# audio-mixer-smd.net
KiCad netlist of a schematic drawn in EAGLE
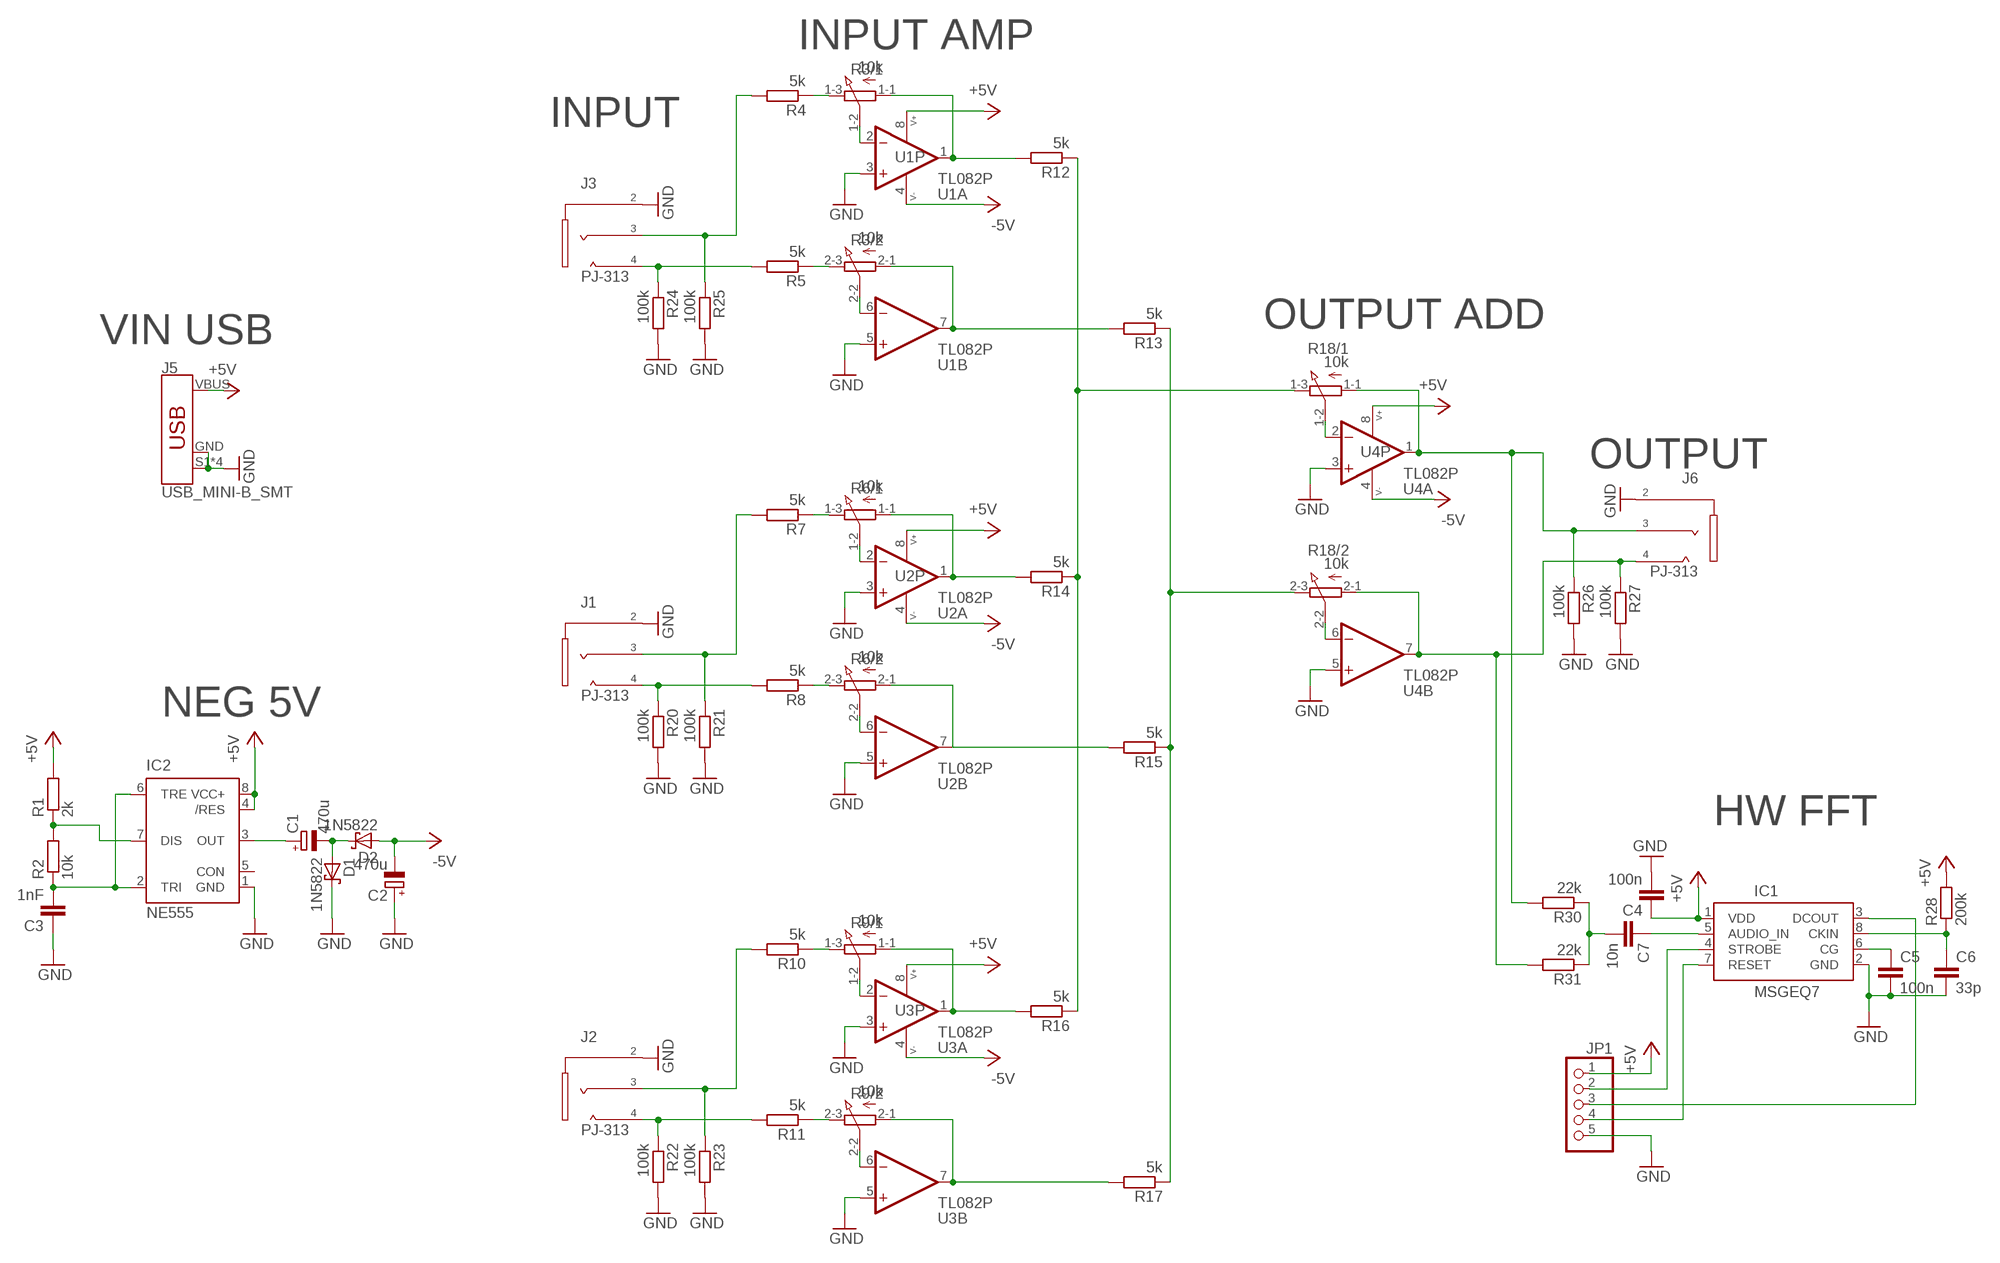
[diagram p0: schematic, sheet 1]

(export (version "E")
  (design (tool "Eeschema 10.0.6"))
  (components
    (comp (ref "C1")
      (value "470u")
      (footprint "eagle-import:E5-8,5")
      (libsource (lib "eagle-import") (part "CPOL-EUE5-8.5"))
    )
    (comp (ref "C2")
      (value "470u")
      (footprint "eagle-import:E5-8,5")
      (libsource (lib "eagle-import") (part "CPOL-EUE5-8.5"))
    )
    (comp (ref "C3")
      (value "1nF")
      (footprint "eagle-import:C0805")
      (libsource (lib "eagle-import") (part "C-EUC0805"))
    )
    (comp (ref "C4")
      (value "100n")
      (footprint "eagle-import:C0805")
      (libsource (lib "eagle-import") (part "C-EUC0805"))
    )
    (comp (ref "C5")
      (value "100n")
      (footprint "eagle-import:C0805")
      (libsource (lib "eagle-import") (part "C-EUC0805"))
    )
    (comp (ref "C6")
      (value "33p")
      (footprint "eagle-import:C0805")
      (libsource (lib "eagle-import") (part "C-EUC0805"))
    )
    (comp (ref "C7")
      (value "10n")
      (footprint "eagle-import:C0805")
      (libsource (lib "eagle-import") (part "C-EUC0805"))
    )
    (comp (ref "D1")
      (value "1N5822")
      (footprint "eagle-import:DO41-7.6")
      (libsource (lib "eagle-import") (part "1N5817-B"))
    )
    (comp (ref "D2")
      (value "1N5822")
      (footprint "eagle-import:DO41-7.6")
      (libsource (lib "eagle-import") (part "1N5817-B"))
    )
    (comp (ref "IC1")
      (value "MSGEQ7DIP")
      (footprint "eagle-import:DIL08")
      (libsource (lib "eagle-import") (part "MSGEQ7DIP"))
    )
    (comp (ref "IC2")
      (value "NE555")
      (footprint "eagle-import:DIL-08")
      (fields (field (name "MF") "Arrow Electronics") (field (name "MPN") "NE555N"))
      (libsource (lib "eagle-import") (part "NE555"))
    )
    (comp (ref "J1")
      (value "PJ-313")
      (footprint "eagle-import:PJ-313")
      (libsource (lib "eagle-import") (part "PJ-313"))
    )
    (comp (ref "J2")
      (value "PJ-313")
      (footprint "eagle-import:PJ-313")
      (libsource (lib "eagle-import") (part "PJ-313"))
    )
    (comp (ref "J3")
      (value "PJ-313")
      (footprint "eagle-import:PJ-313")
      (libsource (lib "eagle-import") (part "PJ-313"))
    )
    (comp (ref "J5")
      (value "USB_MINI-B_SMT")
      (footprint "eagle-import:USB-MINIB")
      (libsource (lib "eagle-import") (part "USB_MINI-B_SMT"))
    )
    (comp (ref "J6")
      (value "PJ-313")
      (footprint "eagle-import:PJ-313")
      (libsource (lib "eagle-import") (part "PJ-313"))
    )
    (comp (ref "JP1")
      (value "PINHD-1X05_2.54-S")
      (footprint "eagle-import:1X05-S")
      (libsource (lib "eagle-import") (part "PINHD-1X05_2.54-S"))
    )
    (comp (ref "R1")
      (value "2k")
      (footprint "eagle-import:R0805")
      (libsource (lib "eagle-import") (part "R-EU_R0805"))
    )
    (comp (ref "R2")
      (value "10k")
      (footprint "eagle-import:R0805")
      (libsource (lib "eagle-import") (part "R-EU_R0805"))
    )
    (comp (ref "R3")
      (value "10k")
      (footprint "eagle-import:3RP_1610G")
      (libsource (lib "eagle-import") (part "3RP/1610G"))
    )
    (comp (ref "R4")
      (value "5k")
      (footprint "eagle-import:R0805")
      (libsource (lib "eagle-import") (part "R-EU_R0805"))
    )
    (comp (ref "R5")
      (value "5k")
      (footprint "eagle-import:R0805")
      (libsource (lib "eagle-import") (part "R-EU_R0805"))
    )
    (comp (ref "R6")
      (value "10k")
      (footprint "eagle-import:3RP_1610G")
      (libsource (lib "eagle-import") (part "3RP/1610G"))
    )
    (comp (ref "R7")
      (value "5k")
      (footprint "eagle-import:R0805")
      (libsource (lib "eagle-import") (part "R-EU_R0805"))
    )
    (comp (ref "R8")
      (value "5k")
      (footprint "eagle-import:R0805")
      (libsource (lib "eagle-import") (part "R-EU_R0805"))
    )
    (comp (ref "R9")
      (value "10k")
      (footprint "eagle-import:3RP_1610G")
      (libsource (lib "eagle-import") (part "3RP/1610G"))
    )
    (comp (ref "R10")
      (value "5k")
      (footprint "eagle-import:R0805")
      (libsource (lib "eagle-import") (part "R-EU_R0805"))
    )
    (comp (ref "R11")
      (value "5k")
      (footprint "eagle-import:R0805")
      (libsource (lib "eagle-import") (part "R-EU_R0805"))
    )
    (comp (ref "R12")
      (value "5k")
      (footprint "eagle-import:R0805")
      (libsource (lib "eagle-import") (part "R-EU_R0805"))
    )
    (comp (ref "R13")
      (value "5k")
      (footprint "eagle-import:R0805")
      (libsource (lib "eagle-import") (part "R-EU_R0805"))
    )
    (comp (ref "R14")
      (value "5k")
      (footprint "eagle-import:R0805")
      (libsource (lib "eagle-import") (part "R-EU_R0805"))
    )
    (comp (ref "R15")
      (value "5k")
      (footprint "eagle-import:R0805")
      (libsource (lib "eagle-import") (part "R-EU_R0805"))
    )
    (comp (ref "R16")
      (value "5k")
      (footprint "eagle-import:R0805")
      (libsource (lib "eagle-import") (part "R-EU_R0805"))
    )
    (comp (ref "R17")
      (value "5k")
      (footprint "eagle-import:R0805")
      (libsource (lib "eagle-import") (part "R-EU_R0805"))
    )
    (comp (ref "R18")
      (value "10k")
      (footprint "eagle-import:3RP_1610G")
      (libsource (lib "eagle-import") (part "3RP/1610G"))
    )
    (comp (ref "R20")
      (value "100k")
      (footprint "eagle-import:R0805")
      (libsource (lib "eagle-import") (part "R-EU_R0805"))
    )
    (comp (ref "R21")
      (value "100k")
      (footprint "eagle-import:R0805")
      (libsource (lib "eagle-import") (part "R-EU_R0805"))
    )
    (comp (ref "R22")
      (value "100k")
      (footprint "eagle-import:R0805")
      (libsource (lib "eagle-import") (part "R-EU_R0805"))
    )
    (comp (ref "R23")
      (value "100k")
      (footprint "eagle-import:R0805")
      (libsource (lib "eagle-import") (part "R-EU_R0805"))
    )
    (comp (ref "R24")
      (value "100k")
      (footprint "eagle-import:R0805")
      (libsource (lib "eagle-import") (part "R-EU_R0805"))
    )
    (comp (ref "R25")
      (value "100k")
      (footprint "eagle-import:R0805")
      (libsource (lib "eagle-import") (part "R-EU_R0805"))
    )
    (comp (ref "R26")
      (value "100k")
      (footprint "eagle-import:R0805")
      (libsource (lib "eagle-import") (part "R-EU_R0805"))
    )
    (comp (ref "R27")
      (value "100k")
      (footprint "eagle-import:R0805")
      (libsource (lib "eagle-import") (part "R-EU_R0805"))
    )
    (comp (ref "R28")
      (value "200k")
      (footprint "eagle-import:R0805")
      (libsource (lib "eagle-import") (part "R-EU_R0805"))
    )
    (comp (ref "R30")
      (value "22k")
      (footprint "eagle-import:R0805")
      (libsource (lib "eagle-import") (part "R-EU_R0805"))
    )
    (comp (ref "R31")
      (value "22k")
      (footprint "eagle-import:R0805")
      (libsource (lib "eagle-import") (part "R-EU_R0805"))
    )
    (comp (ref "U1")
      (value "TL082P")
      (footprint "eagle-import:DIL08")
      (libsource (lib "eagle-import") (part "TL082P"))
    )
    (comp (ref "U2")
      (value "TL082P")
      (footprint "eagle-import:DIL08")
      (libsource (lib "eagle-import") (part "TL082P"))
    )
    (comp (ref "U3")
      (value "TL082P")
      (footprint "eagle-import:DIL08")
      (libsource (lib "eagle-import") (part "TL082P"))
    )
    (comp (ref "U4")
      (value "TL082P")
      (footprint "eagle-import:DIL08")
      (libsource (lib "eagle-import") (part "TL082P"))
    )
  )
  (nets
    (net (code "1") (name "+5V") (class "Default")
      (node (ref "C4") (pin "1") (pinfunction "1_1") (pintype "passive"))
      (node (ref "IC1") (pin "1") (pinfunction "VDD_1") (pintype "input"))
      (node (ref "IC2") (pin "4") (pinfunction "/RES_4") (pintype "input"))
      (node (ref "IC2") (pin "8") (pinfunction "VCC+_8") (pintype "power_in"))
      (node (ref "J5") (pin "VBUS") (pinfunction "VBUS_VBUS") (pintype "power_in"))
      (node (ref "JP1") (pin "1") (pinfunction "1_1") (pintype "passive"))
      (node (ref "R1") (pin "2") (pinfunction "2_2") (pintype "passive"))
      (node (ref "R28") (pin "2") (pinfunction "2_2") (pintype "passive"))
      (node (ref "U1") (pin "8") (pinfunction "V+_8") (pintype "power_in"))
      (node (ref "U2") (pin "8") (pinfunction "V+_8") (pintype "power_in"))
      (node (ref "U3") (pin "8") (pinfunction "V+_8") (pintype "power_in"))
      (node (ref "U4") (pin "8") (pinfunction "V+_8") (pintype "power_in"))
    )
    (net (code "2") (name "-5V") (class "Default")
      (node (ref "C2") (pin "-") (pinfunction "-_-") (pintype "passive"))
      (node (ref "D2") (pin "A") (pinfunction "A_A") (pintype "passive"))
      (node (ref "U1") (pin "4") (pinfunction "V-_4") (pintype "power_in"))
      (node (ref "U2") (pin "4") (pinfunction "V-_4") (pintype "power_in"))
      (node (ref "U3") (pin "4") (pinfunction "V-_4") (pintype "power_in"))
      (node (ref "U4") (pin "4") (pinfunction "V-_4") (pintype "power_in"))
    )
    (net (code "3") (name "GND") (class "Default")
      (node (ref "C2") (pin "+") (pinfunction "+_+") (pintype "passive"))
      (node (ref "C3") (pin "1") (pinfunction "1_1") (pintype "passive"))
      (node (ref "C4") (pin "2") (pinfunction "2_2") (pintype "passive"))
      (node (ref "C5") (pin "2") (pinfunction "2_2") (pintype "passive"))
      (node (ref "C6") (pin "2") (pinfunction "2_2") (pintype "passive"))
      (node (ref "D1") (pin "C") (pinfunction "C_C") (pintype "passive"))
      (node (ref "IC1") (pin "2") (pinfunction "GND_2") (pintype "bidirectional"))
      (node (ref "IC2") (pin "1") (pinfunction "GND_1") (pintype "power_in"))
      (node (ref "J1") (pin "2_1") (pinfunction "2_2_1") (pintype "passive"))
      (node (ref "J1") (pin "2_2") (pinfunction "2_2_2") (pintype "passive"))
      (node (ref "J2") (pin "2_1") (pinfunction "2_2_1") (pintype "passive"))
      (node (ref "J2") (pin "2_2") (pinfunction "2_2_2") (pintype "passive"))
      (node (ref "J3") (pin "2_1") (pinfunction "2_2_1") (pintype "passive"))
      (node (ref "J3") (pin "2_2") (pinfunction "2_2_2") (pintype "passive"))
      (node (ref "J5") (pin "GND") (pinfunction "GND_GND") (pintype "power_in"))
      (node (ref "J5") (pin "S1") (pinfunction "SHIELD_S1") (pintype "bidirectional"))
      (node (ref "J5") (pin "S2") (pinfunction "SHIELD_S2") (pintype "bidirectional"))
      (node (ref "J5") (pin "S3") (pinfunction "SHIELD_S3") (pintype "bidirectional"))
      (node (ref "J5") (pin "S4") (pinfunction "SHIELD_S4") (pintype "bidirectional"))
      (node (ref "J6") (pin "2_1") (pinfunction "2_2_1") (pintype "passive"))
      (node (ref "J6") (pin "2_2") (pinfunction "2_2_2") (pintype "passive"))
      (node (ref "JP1") (pin "5") (pinfunction "5_5") (pintype "passive"))
      (node (ref "R20") (pin "2") (pinfunction "2_2") (pintype "passive"))
      (node (ref "R21") (pin "2") (pinfunction "2_2") (pintype "passive"))
      (node (ref "R22") (pin "2") (pinfunction "2_2") (pintype "passive"))
      (node (ref "R23") (pin "2") (pinfunction "2_2") (pintype "passive"))
      (node (ref "R24") (pin "2") (pinfunction "2_2") (pintype "passive"))
      (node (ref "R25") (pin "2") (pinfunction "2_2") (pintype "passive"))
      (node (ref "R26") (pin "2") (pinfunction "2_2") (pintype "passive"))
      (node (ref "R27") (pin "2") (pinfunction "2_2") (pintype "passive"))
      (node (ref "U1") (pin "3") (pinfunction "+IN_3") (pintype "input"))
      (node (ref "U1") (pin "5") (pinfunction "+IN_5") (pintype "input"))
      (node (ref "U2") (pin "3") (pinfunction "+IN_3") (pintype "input"))
      (node (ref "U2") (pin "5") (pinfunction "+IN_5") (pintype "input"))
      (node (ref "U3") (pin "3") (pinfunction "+IN_3") (pintype "input"))
      (node (ref "U3") (pin "5") (pinfunction "+IN_5") (pintype "input"))
      (node (ref "U4") (pin "3") (pinfunction "+IN_3") (pintype "input"))
      (node (ref "U4") (pin "5") (pinfunction "+IN_5") (pintype "input"))
    )
    (net (code "4") (name "Net-(C1-Pad-)") (class "Default")
      (node (ref "C1") (pin "-") (pinfunction "-_-") (pintype "passive"))
      (node (ref "D1") (pin "A") (pinfunction "A_A") (pintype "passive"))
      (node (ref "D2") (pin "C") (pinfunction "C_C") (pintype "passive"))
    )
    (net (code "5") (name "Net-(C7-Pad2)") (class "Default")
      (node (ref "C7") (pin "2") (pinfunction "2_2") (pintype "passive"))
      (node (ref "R30") (pin "1") (pinfunction "1_1") (pintype "passive"))
      (node (ref "R31") (pin "1") (pinfunction "1_1") (pintype "passive"))
    )
    (net (code "6") (name "Net-(IC1-AUDIO_IN)") (class "Default")
      (node (ref "C7") (pin "1") (pinfunction "1_1") (pintype "passive"))
      (node (ref "IC1") (pin "5") (pinfunction "AUDIO_IN_5") (pintype "input"))
    )
    (net (code "7") (name "Net-(IC1-CG)") (class "Default")
      (node (ref "C5") (pin "1") (pinfunction "1_1") (pintype "passive"))
      (node (ref "IC1") (pin "6") (pinfunction "CG_6") (pintype "bidirectional"))
    )
    (net (code "8") (name "Net-(IC1-CKIN)") (class "Default")
      (node (ref "C6") (pin "1") (pinfunction "1_1") (pintype "passive"))
      (node (ref "IC1") (pin "8") (pinfunction "CKIN_8") (pintype "bidirectional"))
      (node (ref "R28") (pin "1") (pinfunction "1_1") (pintype "passive"))
    )
    (net (code "9") (name "Net-(IC1-DCOUT)") (class "Default")
      (node (ref "IC1") (pin "3") (pinfunction "DCOUT_3") (pintype "bidirectional"))
      (node (ref "JP1") (pin "3") (pinfunction "3_3") (pintype "passive"))
    )
    (net (code "10") (name "Net-(IC1-RESET)") (class "Default")
      (node (ref "IC1") (pin "7") (pinfunction "RESET_7") (pintype "input"))
      (node (ref "JP1") (pin "4") (pinfunction "4_4") (pintype "passive"))
    )
    (net (code "11") (name "Net-(IC1-STROBE)") (class "Default")
      (node (ref "IC1") (pin "4") (pinfunction "STROBE_4") (pintype "input"))
      (node (ref "JP1") (pin "2") (pinfunction "2_2") (pintype "passive"))
    )
    (net (code "12") (name "Net-(IC2-DIS)") (class "Default")
      (node (ref "IC2") (pin "7") (pinfunction "DIS_7") (pintype "input"))
      (node (ref "R1") (pin "1") (pinfunction "1_1") (pintype "passive"))
      (node (ref "R2") (pin "2") (pinfunction "2_2") (pintype "passive"))
    )
    (net (code "13") (name "Net-(IC2-OUT)") (class "Default")
      (node (ref "C1") (pin "+") (pinfunction "+_+") (pintype "passive"))
      (node (ref "IC2") (pin "3") (pinfunction "OUT_3") (pintype "output"))
    )
    (net (code "14") (name "Net-(IC2-TRE)") (class "Default")
      (node (ref "C3") (pin "2") (pinfunction "2_2") (pintype "passive"))
      (node (ref "IC2") (pin "2") (pinfunction "TRI_2") (pintype "input"))
      (node (ref "IC2") (pin "6") (pinfunction "TRE_6") (pintype "input"))
      (node (ref "R2") (pin "1") (pinfunction "1_1") (pintype "passive"))
    )
    (net (code "15") (name "Net-(J1-4-Pad4_1)") (class "Default")
      (node (ref "J1") (pin "4_1") (pinfunction "4_4_1") (pintype "passive"))
      (node (ref "J1") (pin "4_2") (pinfunction "4_4_2") (pintype "passive"))
      (node (ref "R20") (pin "1") (pinfunction "1_1") (pintype "passive"))
      (node (ref "R8") (pin "2") (pinfunction "2_2") (pintype "passive"))
    )
    (net (code "16") (name "Net-(J1-Pad3)") (class "Default")
      (node (ref "J1") (pin "3") (pinfunction "3_3") (pintype "passive"))
      (node (ref "R21") (pin "1") (pinfunction "1_1") (pintype "passive"))
      (node (ref "R7") (pin "2") (pinfunction "2_2") (pintype "passive"))
    )
    (net (code "17") (name "Net-(J2-4-Pad4_1)") (class "Default")
      (node (ref "J2") (pin "4_1") (pinfunction "4_4_1") (pintype "passive"))
      (node (ref "J2") (pin "4_2") (pinfunction "4_4_2") (pintype "passive"))
      (node (ref "R11") (pin "2") (pinfunction "2_2") (pintype "passive"))
      (node (ref "R22") (pin "1") (pinfunction "1_1") (pintype "passive"))
    )
    (net (code "18") (name "Net-(J2-Pad3)") (class "Default")
      (node (ref "J2") (pin "3") (pinfunction "3_3") (pintype "passive"))
      (node (ref "R10") (pin "2") (pinfunction "2_2") (pintype "passive"))
      (node (ref "R23") (pin "1") (pinfunction "1_1") (pintype "passive"))
    )
    (net (code "19") (name "Net-(J3-4-Pad4_1)") (class "Default")
      (node (ref "J3") (pin "4_1") (pinfunction "4_4_1") (pintype "passive"))
      (node (ref "J3") (pin "4_2") (pinfunction "4_4_2") (pintype "passive"))
      (node (ref "R24") (pin "1") (pinfunction "1_1") (pintype "passive"))
      (node (ref "R5") (pin "2") (pinfunction "2_2") (pintype "passive"))
    )
    (net (code "20") (name "Net-(J3-Pad3)") (class "Default")
      (node (ref "J3") (pin "3") (pinfunction "3_3") (pintype "passive"))
      (node (ref "R25") (pin "1") (pinfunction "1_1") (pintype "passive"))
      (node (ref "R4") (pin "2") (pinfunction "2_2") (pintype "passive"))
    )
    (net (code "21") (name "Net-(R3A-A)") (class "Default")
      (node (ref "R12") (pin "2") (pinfunction "2_2") (pintype "passive"))
      (node (ref "R3") (pin "1-1") (pinfunction "A_1-1") (pintype "passive"))
      (node (ref "U1") (pin "1") (pinfunction "OUT_1") (pintype "output"))
    )
    (net (code "22") (name "Net-(R3A-E)") (class "Default")
      (node (ref "R3") (pin "1-3") (pinfunction "E_1-3") (pintype "passive"))
      (node (ref "R4") (pin "1") (pinfunction "1_1") (pintype "passive"))
    )
    (net (code "23") (name "Net-(R3A-S)") (class "Default")
      (node (ref "R3") (pin "1-2") (pinfunction "S_1-2") (pintype "passive"))
      (node (ref "U1") (pin "2") (pinfunction "-IN_2") (pintype "input"))
    )
    (net (code "24") (name "Net-(R3B-A)") (class "Default")
      (node (ref "R13") (pin "2") (pinfunction "2_2") (pintype "passive"))
      (node (ref "R3") (pin "2-1") (pinfunction "A_2-1") (pintype "passive"))
      (node (ref "U1") (pin "7") (pinfunction "OUT_7") (pintype "output"))
    )
    (net (code "25") (name "Net-(R3B-E)") (class "Default")
      (node (ref "R3") (pin "2-3") (pinfunction "E_2-3") (pintype "passive"))
      (node (ref "R5") (pin "1") (pinfunction "1_1") (pintype "passive"))
    )
    (net (code "26") (name "Net-(R3B-S)") (class "Default")
      (node (ref "R3") (pin "2-2") (pinfunction "S_2-2") (pintype "passive"))
      (node (ref "U1") (pin "6") (pinfunction "-IN_6") (pintype "input"))
    )
    (net (code "27") (name "Net-(R6A-A)") (class "Default")
      (node (ref "R14") (pin "2") (pinfunction "2_2") (pintype "passive"))
      (node (ref "R6") (pin "1-1") (pinfunction "A_1-1") (pintype "passive"))
      (node (ref "U2") (pin "1") (pinfunction "OUT_1") (pintype "output"))
    )
    (net (code "28") (name "Net-(R6A-E)") (class "Default")
      (node (ref "R6") (pin "1-3") (pinfunction "E_1-3") (pintype "passive"))
      (node (ref "R7") (pin "1") (pinfunction "1_1") (pintype "passive"))
    )
    (net (code "29") (name "Net-(R6A-S)") (class "Default")
      (node (ref "R6") (pin "1-2") (pinfunction "S_1-2") (pintype "passive"))
      (node (ref "U2") (pin "2") (pinfunction "-IN_2") (pintype "input"))
    )
    (net (code "30") (name "Net-(R6B-A)") (class "Default")
      (node (ref "R15") (pin "2") (pinfunction "2_2") (pintype "passive"))
      (node (ref "R6") (pin "2-1") (pinfunction "A_2-1") (pintype "passive"))
      (node (ref "U2") (pin "7") (pinfunction "OUT_7") (pintype "output"))
    )
    (net (code "31") (name "Net-(R6B-E)") (class "Default")
      (node (ref "R6") (pin "2-3") (pinfunction "E_2-3") (pintype "passive"))
      (node (ref "R8") (pin "1") (pinfunction "1_1") (pintype "passive"))
    )
    (net (code "32") (name "Net-(R6B-S)") (class "Default")
      (node (ref "R6") (pin "2-2") (pinfunction "S_2-2") (pintype "passive"))
      (node (ref "U2") (pin "6") (pinfunction "-IN_6") (pintype "input"))
    )
    (net (code "33") (name "Net-(R9A-A)") (class "Default")
      (node (ref "R16") (pin "2") (pinfunction "2_2") (pintype "passive"))
      (node (ref "R9") (pin "1-1") (pinfunction "A_1-1") (pintype "passive"))
      (node (ref "U3") (pin "1") (pinfunction "OUT_1") (pintype "output"))
    )
    (net (code "34") (name "Net-(R9A-E)") (class "Default")
      (node (ref "R10") (pin "1") (pinfunction "1_1") (pintype "passive"))
      (node (ref "R9") (pin "1-3") (pinfunction "E_1-3") (pintype "passive"))
    )
    (net (code "35") (name "Net-(R9A-S)") (class "Default")
      (node (ref "R9") (pin "1-2") (pinfunction "S_1-2") (pintype "passive"))
      (node (ref "U3") (pin "2") (pinfunction "-IN_2") (pintype "input"))
    )
    (net (code "36") (name "Net-(R9B-A)") (class "Default")
      (node (ref "R17") (pin "2") (pinfunction "2_2") (pintype "passive"))
      (node (ref "R9") (pin "2-1") (pinfunction "A_2-1") (pintype "passive"))
      (node (ref "U3") (pin "7") (pinfunction "OUT_7") (pintype "output"))
    )
    (net (code "37") (name "Net-(R9B-E)") (class "Default")
      (node (ref "R11") (pin "1") (pinfunction "1_1") (pintype "passive"))
      (node (ref "R9") (pin "2-3") (pinfunction "E_2-3") (pintype "passive"))
    )
    (net (code "38") (name "Net-(R9B-S)") (class "Default")
      (node (ref "R9") (pin "2-2") (pinfunction "S_2-2") (pintype "passive"))
      (node (ref "U3") (pin "6") (pinfunction "-IN_6") (pintype "input"))
    )
    (net (code "39") (name "Net-(R18A-A)") (class "Default")
      (node (ref "J6") (pin "3") (pinfunction "3_3") (pintype "passive"))
      (node (ref "R18") (pin "1-1") (pinfunction "A_1-1") (pintype "passive"))
      (node (ref "R26") (pin "1") (pinfunction "1_1") (pintype "passive"))
      (node (ref "R30") (pin "2") (pinfunction "2_2") (pintype "passive"))
      (node (ref "U4") (pin "1") (pinfunction "OUT_1") (pintype "output"))
    )
    (net (code "40") (name "Net-(R18A-E)") (class "Default")
      (node (ref "R12") (pin "1") (pinfunction "1_1") (pintype "passive"))
      (node (ref "R14") (pin "1") (pinfunction "1_1") (pintype "passive"))
      (node (ref "R16") (pin "1") (pinfunction "1_1") (pintype "passive"))
      (node (ref "R18") (pin "1-3") (pinfunction "E_1-3") (pintype "passive"))
    )
    (net (code "41") (name "Net-(R18A-S)") (class "Default")
      (node (ref "R18") (pin "1-2") (pinfunction "S_1-2") (pintype "passive"))
      (node (ref "U4") (pin "2") (pinfunction "-IN_2") (pintype "input"))
    )
    (net (code "42") (name "Net-(R18B-A)") (class "Default")
      (node (ref "J6") (pin "4_1") (pinfunction "4_4_1") (pintype "passive"))
      (node (ref "J6") (pin "4_2") (pinfunction "4_4_2") (pintype "passive"))
      (node (ref "R18") (pin "2-1") (pinfunction "A_2-1") (pintype "passive"))
      (node (ref "R27") (pin "1") (pinfunction "1_1") (pintype "passive"))
      (node (ref "R31") (pin "2") (pinfunction "2_2") (pintype "passive"))
      (node (ref "U4") (pin "7") (pinfunction "OUT_7") (pintype "output"))
    )
    (net (code "43") (name "Net-(R18B-E)") (class "Default")
      (node (ref "R13") (pin "1") (pinfunction "1_1") (pintype "passive"))
      (node (ref "R15") (pin "1") (pinfunction "1_1") (pintype "passive"))
      (node (ref "R17") (pin "1") (pinfunction "1_1") (pintype "passive"))
      (node (ref "R18") (pin "2-3") (pinfunction "E_2-3") (pintype "passive"))
    )
    (net (code "44") (name "Net-(R18B-S)") (class "Default")
      (node (ref "R18") (pin "2-2") (pinfunction "S_2-2") (pintype "passive"))
      (node (ref "U4") (pin "6") (pinfunction "-IN_6") (pintype "input"))
    )
    (net (code "45") (name "unconnected-(IC2-CON-Pad5)") (class "Default")
      (node (ref "IC2") (pin "5") (pinfunction "CON_5") (pintype "input"))
    )
  )
)
